# SCH_interface_cmv4000-de2.net
KiCad netlist of a schematic drawn in Altium Designer
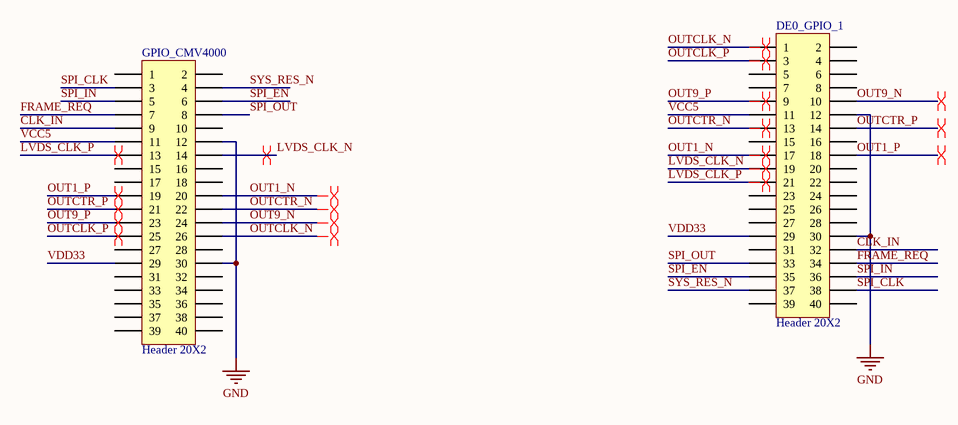
[diagram p0: SCH_interface_cmv4000-de2.SchDoc]

(export (version "E")
  (design (tool "Eeschema 10.0.6"))
  (components
    (comp (ref "DE0_GPIO_1")
      (value "Header 20X2")
      (footprint "HDR2X20")
      (description "Header, 20-Pin, Dual row")
      (fields (field (name "PUBLISHER") "Altium Limited"))
      (libsource (lib "Miscellaneous Connectors") (part "Header 20X2"))
    )
    (comp (ref "GPIO_CMV4000")
      (value "Header 20X2")
      (footprint "HDR2X20")
      (description "Header, 20-Pin, Dual row")
      (fields (field (name "PUBLISHER") "Altium Limited"))
      (libsource (lib "Miscellaneous Connectors") (part "Header 20X2"))
    )
  )
  (nets
    (net (code "1") (name "/CLK_IN") (class "Default")
      (node (ref "DE0_GPIO_1") (pin "32") (pinfunction "32_32") (pintype "passive"))
      (node (ref "GPIO_CMV4000") (pin "9") (pinfunction "9_9") (pintype "passive"))
    )
    (net (code "2") (name "/FRAME_REQ") (class "Default")
      (node (ref "DE0_GPIO_1") (pin "34") (pinfunction "34_34") (pintype "passive"))
      (node (ref "GPIO_CMV4000") (pin "7") (pinfunction "7_7") (pintype "passive"))
    )
    (net (code "3") (name "/LVDS_CLK_N") (class "Default")
      (node (ref "DE0_GPIO_1") (pin "19") (pinfunction "19_19") (pintype "passive"))
      (node (ref "GPIO_CMV4000") (pin "14") (pinfunction "14_14") (pintype "passive"))
    )
    (net (code "4") (name "/LVDS_CLK_P") (class "Default")
      (node (ref "DE0_GPIO_1") (pin "21") (pinfunction "21_21") (pintype "passive"))
      (node (ref "GPIO_CMV4000") (pin "13") (pinfunction "13_13") (pintype "passive"))
    )
    (net (code "5") (name "/OUT1_N") (class "Default")
      (node (ref "DE0_GPIO_1") (pin "17") (pinfunction "17_17") (pintype "passive"))
      (node (ref "GPIO_CMV4000") (pin "20") (pinfunction "20_20") (pintype "passive"))
    )
    (net (code "6") (name "/OUT1_P") (class "Default")
      (node (ref "DE0_GPIO_1") (pin "18") (pinfunction "18_18") (pintype "passive"))
      (node (ref "GPIO_CMV4000") (pin "19") (pinfunction "19_19") (pintype "passive"))
    )
    (net (code "7") (name "/OUT9_N") (class "Default")
      (node (ref "DE0_GPIO_1") (pin "10") (pinfunction "10_10") (pintype "passive"))
      (node (ref "GPIO_CMV4000") (pin "24") (pinfunction "24_24") (pintype "passive"))
    )
    (net (code "8") (name "/OUT9_P") (class "Default")
      (node (ref "DE0_GPIO_1") (pin "9") (pinfunction "9_9") (pintype "passive"))
      (node (ref "GPIO_CMV4000") (pin "23") (pinfunction "23_23") (pintype "passive"))
    )
    (net (code "9") (name "/OUTCLK_N") (class "Default")
      (node (ref "DE0_GPIO_1") (pin "1") (pinfunction "1_1") (pintype "passive"))
      (node (ref "GPIO_CMV4000") (pin "26") (pinfunction "26_26") (pintype "passive"))
    )
    (net (code "10") (name "/OUTCLK_P") (class "Default")
      (node (ref "DE0_GPIO_1") (pin "3") (pinfunction "3_3") (pintype "passive"))
      (node (ref "GPIO_CMV4000") (pin "25") (pinfunction "25_25") (pintype "passive"))
    )
    (net (code "11") (name "/OUTCTR_N") (class "Default")
      (node (ref "DE0_GPIO_1") (pin "13") (pinfunction "13_13") (pintype "passive"))
      (node (ref "GPIO_CMV4000") (pin "22") (pinfunction "22_22") (pintype "passive"))
    )
    (net (code "12") (name "/OUTCTR_P") (class "Default")
      (node (ref "DE0_GPIO_1") (pin "14") (pinfunction "14_14") (pintype "passive"))
      (node (ref "GPIO_CMV4000") (pin "21") (pinfunction "21_21") (pintype "passive"))
    )
    (net (code "13") (name "/SPI_CLK") (class "Default")
      (node (ref "DE0_GPIO_1") (pin "38") (pinfunction "38_38") (pintype "passive"))
      (node (ref "GPIO_CMV4000") (pin "3") (pinfunction "3_3") (pintype "passive"))
    )
    (net (code "14") (name "/SPI_EN") (class "Default")
      (node (ref "DE0_GPIO_1") (pin "35") (pinfunction "35_35") (pintype "passive"))
      (node (ref "GPIO_CMV4000") (pin "6") (pinfunction "6_6") (pintype "passive"))
    )
    (net (code "15") (name "/SPI_IN") (class "Default")
      (node (ref "DE0_GPIO_1") (pin "36") (pinfunction "36_36") (pintype "passive"))
      (node (ref "GPIO_CMV4000") (pin "5") (pinfunction "5_5") (pintype "passive"))
    )
    (net (code "16") (name "/SPI_OUT") (class "Default")
      (node (ref "DE0_GPIO_1") (pin "33") (pinfunction "33_33") (pintype "passive"))
      (node (ref "GPIO_CMV4000") (pin "8") (pinfunction "8_8") (pintype "passive"))
    )
    (net (code "17") (name "/SYS_RES_N") (class "Default")
      (node (ref "DE0_GPIO_1") (pin "37") (pinfunction "37_37") (pintype "passive"))
      (node (ref "GPIO_CMV4000") (pin "4") (pinfunction "4_4") (pintype "passive"))
    )
    (net (code "18") (name "/VCC5") (class "Default")
      (node (ref "DE0_GPIO_1") (pin "11") (pinfunction "11_11") (pintype "passive"))
      (node (ref "GPIO_CMV4000") (pin "11") (pinfunction "11_11") (pintype "passive"))
    )
    (net (code "19") (name "/VDD33") (class "Default")
      (node (ref "DE0_GPIO_1") (pin "29") (pinfunction "29_29") (pintype "passive"))
      (node (ref "GPIO_CMV4000") (pin "29") (pinfunction "29_29") (pintype "passive"))
    )
    (net (code "20") (name "GND") (class "Default")
      (node (ref "DE0_GPIO_1") (pin "12") (pinfunction "12_12") (pintype "passive"))
      (node (ref "DE0_GPIO_1") (pin "30") (pinfunction "30_30") (pintype "passive"))
      (node (ref "GPIO_CMV4000") (pin "12") (pinfunction "12_12") (pintype "passive"))
      (node (ref "GPIO_CMV4000") (pin "30") (pinfunction "30_30") (pintype "passive"))
    )
    (net (code "21") (name "unconnected-(DE0_GPIO_1-Pad2)") (class "Default")
      (node (ref "DE0_GPIO_1") (pin "2") (pinfunction "2_2") (pintype "passive"))
    )
    (net (code "22") (name "unconnected-(DE0_GPIO_1-Pad4)") (class "Default")
      (node (ref "DE0_GPIO_1") (pin "4") (pinfunction "4_4") (pintype "passive"))
    )
    (net (code "23") (name "unconnected-(DE0_GPIO_1-Pad5)") (class "Default")
      (node (ref "DE0_GPIO_1") (pin "5") (pinfunction "5_5") (pintype "passive"))
    )
    (net (code "24") (name "unconnected-(DE0_GPIO_1-Pad6)") (class "Default")
      (node (ref "DE0_GPIO_1") (pin "6") (pinfunction "6_6") (pintype "passive"))
    )
    (net (code "25") (name "unconnected-(DE0_GPIO_1-Pad7)") (class "Default")
      (node (ref "DE0_GPIO_1") (pin "7") (pinfunction "7_7") (pintype "passive"))
    )
    (net (code "26") (name "unconnected-(DE0_GPIO_1-Pad8)") (class "Default")
      (node (ref "DE0_GPIO_1") (pin "8") (pinfunction "8_8") (pintype "passive"))
    )
    (net (code "27") (name "unconnected-(DE0_GPIO_1-Pad15)") (class "Default")
      (node (ref "DE0_GPIO_1") (pin "15") (pinfunction "15_15") (pintype "passive"))
    )
    (net (code "28") (name "unconnected-(DE0_GPIO_1-Pad16)") (class "Default")
      (node (ref "DE0_GPIO_1") (pin "16") (pinfunction "16_16") (pintype "passive"))
    )
    (net (code "29") (name "unconnected-(DE0_GPIO_1-Pad20)") (class "Default")
      (node (ref "DE0_GPIO_1") (pin "20") (pinfunction "20_20") (pintype "passive"))
    )
    (net (code "30") (name "unconnected-(DE0_GPIO_1-Pad22)") (class "Default")
      (node (ref "DE0_GPIO_1") (pin "22") (pinfunction "22_22") (pintype "passive"))
    )
    (net (code "31") (name "unconnected-(DE0_GPIO_1-Pad23)") (class "Default")
      (node (ref "DE0_GPIO_1") (pin "23") (pinfunction "23_23") (pintype "passive"))
    )
    (net (code "32") (name "unconnected-(DE0_GPIO_1-Pad24)") (class "Default")
      (node (ref "DE0_GPIO_1") (pin "24") (pinfunction "24_24") (pintype "passive"))
    )
    (net (code "33") (name "unconnected-(DE0_GPIO_1-Pad25)") (class "Default")
      (node (ref "DE0_GPIO_1") (pin "25") (pinfunction "25_25") (pintype "passive"))
    )
    (net (code "34") (name "unconnected-(DE0_GPIO_1-Pad26)") (class "Default")
      (node (ref "DE0_GPIO_1") (pin "26") (pinfunction "26_26") (pintype "passive"))
    )
    (net (code "35") (name "unconnected-(DE0_GPIO_1-Pad27)") (class "Default")
      (node (ref "DE0_GPIO_1") (pin "27") (pinfunction "27_27") (pintype "passive"))
    )
    (net (code "36") (name "unconnected-(DE0_GPIO_1-Pad28)") (class "Default")
      (node (ref "DE0_GPIO_1") (pin "28") (pinfunction "28_28") (pintype "passive"))
    )
    (net (code "37") (name "unconnected-(DE0_GPIO_1-Pad31)") (class "Default")
      (node (ref "DE0_GPIO_1") (pin "31") (pinfunction "31_31") (pintype "passive"))
    )
    (net (code "38") (name "unconnected-(DE0_GPIO_1-Pad39)") (class "Default")
      (node (ref "DE0_GPIO_1") (pin "39") (pinfunction "39_39") (pintype "passive"))
    )
    (net (code "39") (name "unconnected-(DE0_GPIO_1-Pad40)") (class "Default")
      (node (ref "DE0_GPIO_1") (pin "40") (pinfunction "40_40") (pintype "passive"))
    )
    (net (code "40") (name "unconnected-(GPIO_CMV4000-Pad1)") (class "Default")
      (node (ref "GPIO_CMV4000") (pin "1") (pinfunction "1_1") (pintype "passive"))
    )
    (net (code "41") (name "unconnected-(GPIO_CMV4000-Pad2)") (class "Default")
      (node (ref "GPIO_CMV4000") (pin "2") (pinfunction "2_2") (pintype "passive"))
    )
    (net (code "42") (name "unconnected-(GPIO_CMV4000-Pad10)") (class "Default")
      (node (ref "GPIO_CMV4000") (pin "10") (pinfunction "10_10") (pintype "passive"))
    )
    (net (code "43") (name "unconnected-(GPIO_CMV4000-Pad15)") (class "Default")
      (node (ref "GPIO_CMV4000") (pin "15") (pinfunction "15_15") (pintype "passive"))
    )
    (net (code "44") (name "unconnected-(GPIO_CMV4000-Pad16)") (class "Default")
      (node (ref "GPIO_CMV4000") (pin "16") (pinfunction "16_16") (pintype "passive"))
    )
    (net (code "45") (name "unconnected-(GPIO_CMV4000-Pad17)") (class "Default")
      (node (ref "GPIO_CMV4000") (pin "17") (pinfunction "17_17") (pintype "passive"))
    )
    (net (code "46") (name "unconnected-(GPIO_CMV4000-Pad18)") (class "Default")
      (node (ref "GPIO_CMV4000") (pin "18") (pinfunction "18_18") (pintype "passive"))
    )
    (net (code "47") (name "unconnected-(GPIO_CMV4000-Pad27)") (class "Default")
      (node (ref "GPIO_CMV4000") (pin "27") (pinfunction "27_27") (pintype "passive"))
    )
    (net (code "48") (name "unconnected-(GPIO_CMV4000-Pad28)") (class "Default")
      (node (ref "GPIO_CMV4000") (pin "28") (pinfunction "28_28") (pintype "passive"))
    )
    (net (code "49") (name "unconnected-(GPIO_CMV4000-Pad31)") (class "Default")
      (node (ref "GPIO_CMV4000") (pin "31") (pinfunction "31_31") (pintype "passive"))
    )
    (net (code "50") (name "unconnected-(GPIO_CMV4000-Pad32)") (class "Default")
      (node (ref "GPIO_CMV4000") (pin "32") (pinfunction "32_32") (pintype "passive"))
    )
    (net (code "51") (name "unconnected-(GPIO_CMV4000-Pad33)") (class "Default")
      (node (ref "GPIO_CMV4000") (pin "33") (pinfunction "33_33") (pintype "passive"))
    )
    (net (code "52") (name "unconnected-(GPIO_CMV4000-Pad34)") (class "Default")
      (node (ref "GPIO_CMV4000") (pin "34") (pinfunction "34_34") (pintype "passive"))
    )
    (net (code "53") (name "unconnected-(GPIO_CMV4000-Pad35)") (class "Default")
      (node (ref "GPIO_CMV4000") (pin "35") (pinfunction "35_35") (pintype "passive"))
    )
    (net (code "54") (name "unconnected-(GPIO_CMV4000-Pad36)") (class "Default")
      (node (ref "GPIO_CMV4000") (pin "36") (pinfunction "36_36") (pintype "passive"))
    )
    (net (code "55") (name "unconnected-(GPIO_CMV4000-Pad37)") (class "Default")
      (node (ref "GPIO_CMV4000") (pin "37") (pinfunction "37_37") (pintype "passive"))
    )
    (net (code "56") (name "unconnected-(GPIO_CMV4000-Pad38)") (class "Default")
      (node (ref "GPIO_CMV4000") (pin "38") (pinfunction "38_38") (pintype "passive"))
    )
    (net (code "57") (name "unconnected-(GPIO_CMV4000-Pad39)") (class "Default")
      (node (ref "GPIO_CMV4000") (pin "39") (pinfunction "39_39") (pintype "passive"))
    )
    (net (code "58") (name "unconnected-(GPIO_CMV4000-Pad40)") (class "Default")
      (node (ref "GPIO_CMV4000") (pin "40") (pinfunction "40_40") (pintype "passive"))
    )
  )
)
